# PIC32MK1024MCM064.net
KiCad netlist of a schematic drawn in Altium Designer
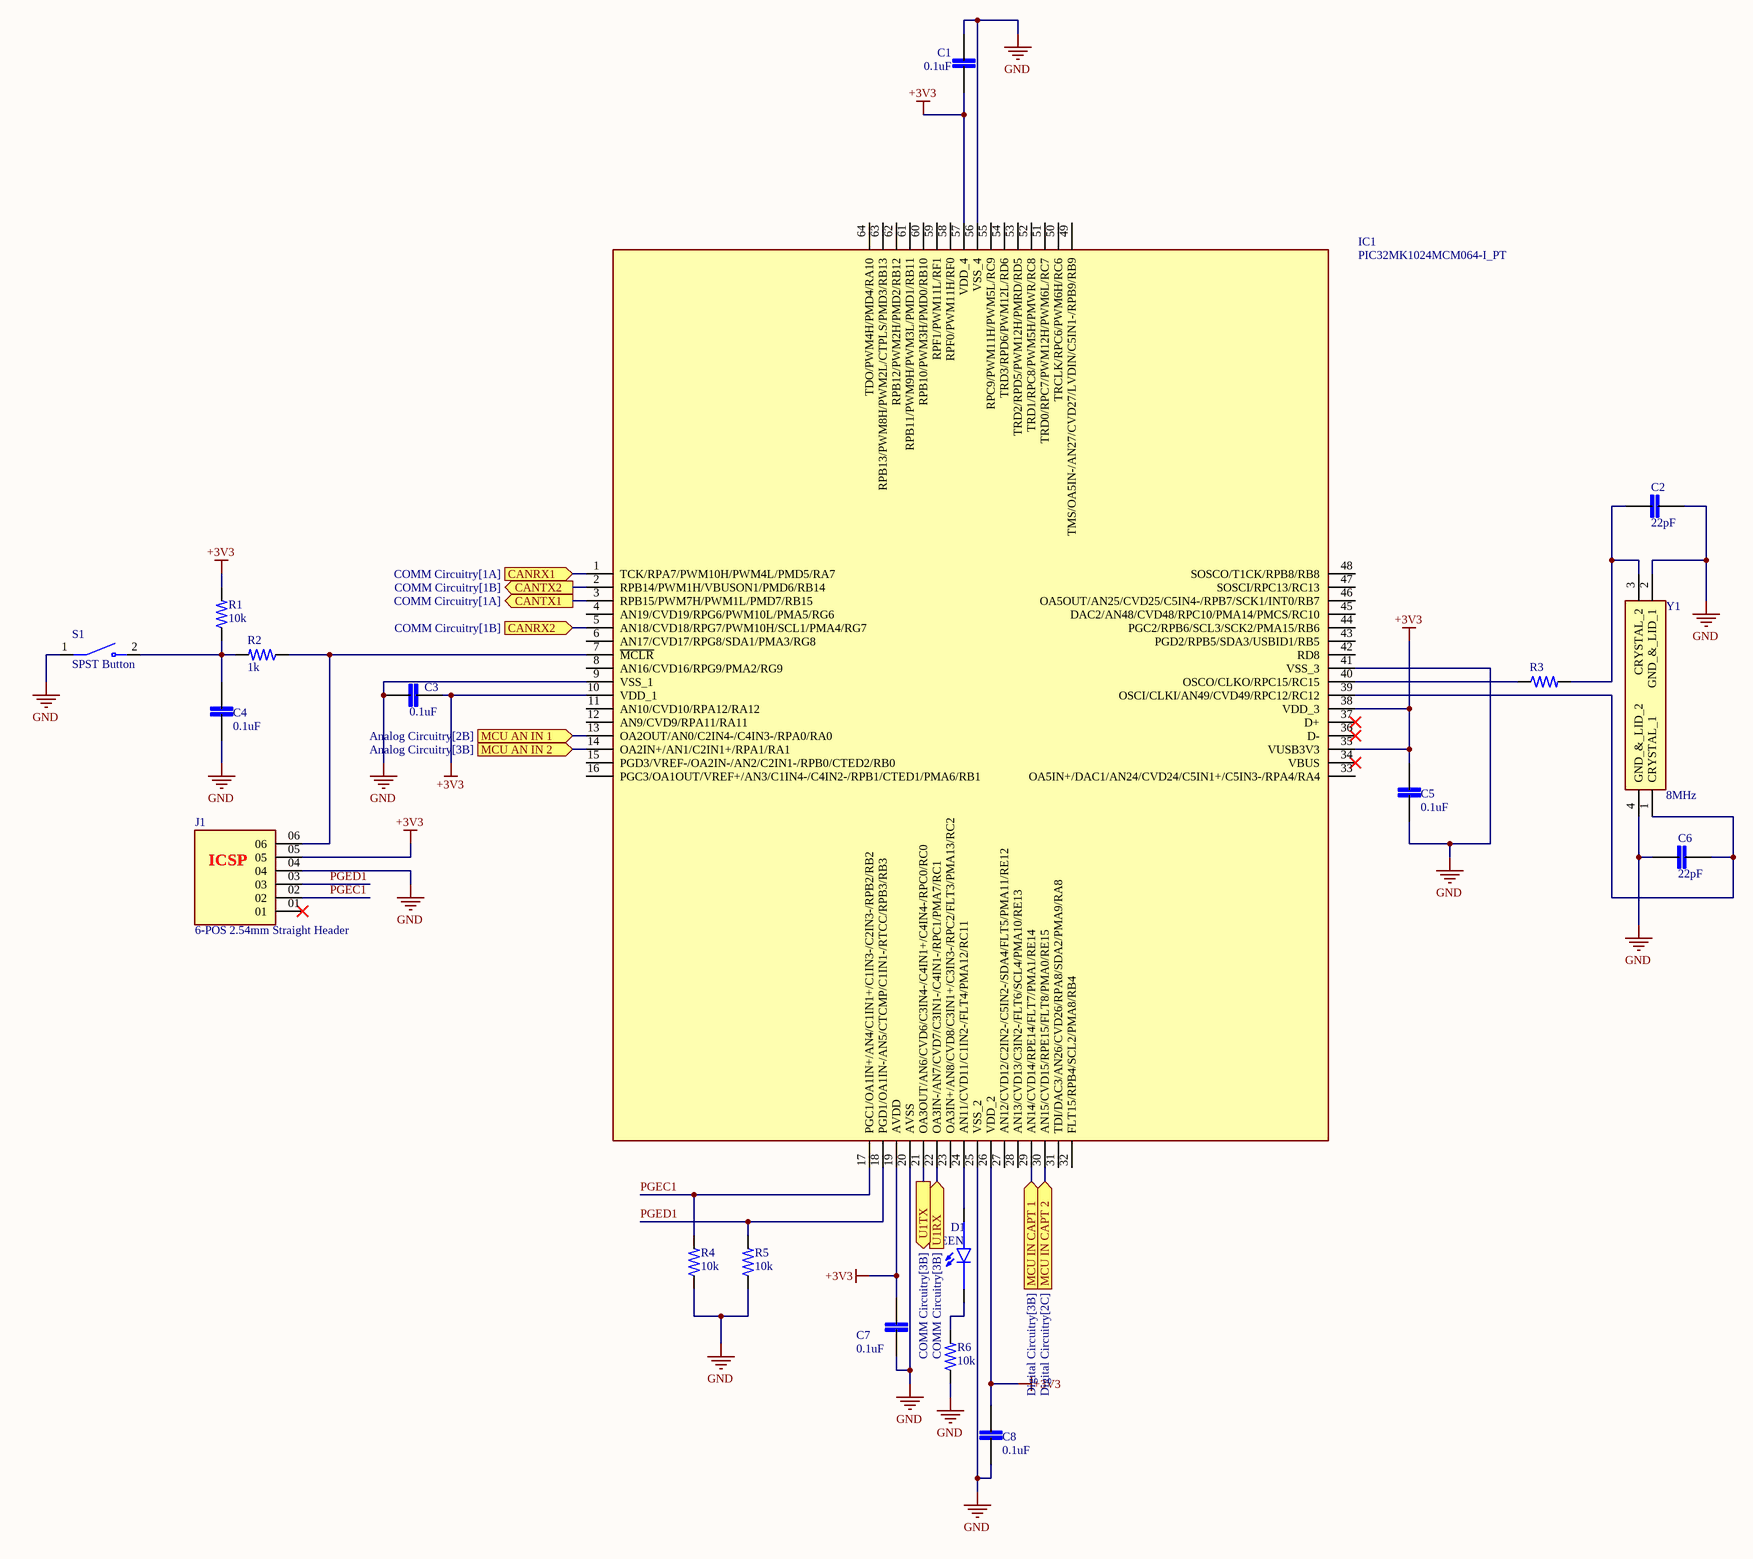
[diagram p0: PIC32MK1024MCM064.SchDoc]

(export (version "E")
  (design (tool "Eeschema 10.0.6"))
  (components
    (comp (ref "C1")
      (value "0.1uF")
      (footprint "0805")
      (fields (field (name "MP") "LD051A121KAB2A") (field (name "MF") "AVX"))
      (libsource (lib "") (part "0805_Capacitor_2"))
    )
    (comp (ref "C2")
      (value "22pF")
      (footprint "0805")
      (fields (field (name "MP") "LD051A121KAB2A") (field (name "MF") "AVX"))
      (libsource (lib "") (part "0805_Capacitor_1"))
    )
    (comp (ref "C3")
      (value "0.1uF")
      (footprint "0805")
      (fields (field (name "MP") "LD051A121KAB2A") (field (name "MF") "AVX"))
      (libsource (lib "") (part "0805_Capacitor_2"))
    )
    (comp (ref "C4")
      (value "0.1uF")
      (footprint "0805")
      (fields (field (name "MP") "LD051A121KAB2A") (field (name "MF") "AVX"))
      (libsource (lib "Capacitors SMD") (part "0805_Capacitor"))
    )
    (comp (ref "C5")
      (value "0.1uF")
      (footprint "0805")
      (fields (field (name "MP") "LD051A121KAB2A") (field (name "MF") "AVX"))
      (libsource (lib "Capacitors SMD") (part "0805_Capacitor"))
    )
    (comp (ref "C6")
      (value "22pF")
      (footprint "0805")
      (fields (field (name "MP") "LD051A121KAB2A") (field (name "MF") "AVX"))
      (libsource (lib "") (part "0805_Capacitor_1"))
    )
    (comp (ref "C7")
      (value "0.1uF")
      (footprint "0805")
      (fields (field (name "MP") "LD051A121KAB2A") (field (name "MF") "AVX"))
      (libsource (lib "Capacitors SMD") (part "0805_Capacitor"))
    )
    (comp (ref "C8")
      (value "0.1uF")
      (footprint "0805")
      (fields (field (name "MP") "LD051A121KAB2A") (field (name "MF") "AVX"))
      (libsource (lib "") (part "0805_Capacitor_1"))
    )
    (comp (ref "D1")
      (value "GREEN")
      (footprint "LED 0805")
      (description "LED Uni-Color Green 4-Pin Chip 0805 T/R")
      (fields (field (name "MP") "597-3305-607F"))
      (libsource (lib "LEDs SMD") (part "LED 0805"))
    )
    (comp (ref "IC1")
      (value "PIC32MK1024MCM064-I_PT")
      (footprint "Microcontrollers:PIC32MK1024MCM064-I_PT")
      (description "Integrated Circuit")
      (fields
        (field (name "MANUFACTURER_PART_NUMBER") "PIC32MK1024MCM064-I/PT")
        (field (name "MOUSER PART NUMBER") "579-2MK1024MCM064IPT")
      )
      (libsource (lib "Microcontrollers") (part "PIC32MK1024MCM064-I_PT"))
    )
    (comp (ref "J1")
      (value "6-POS 2.54mm Straight Header")
      (footprint "6-POS 2.54mm Header")
      (fields (field (name "MP") "HTSW10608SSLA") (field (name "MF") "Samtec"))
      (libsource (lib "Connectors Through Hole") (part "6-POS 2.54mm Straight Header"))
    )
    (comp (ref "R1")
      (value "10k")
      (footprint "0805")
      (fields
        (field (name "MP") "2-2176053-0")
        (field (name "TOLERANCE") "1%")
        (field (name "MF") "TE Connectivity")
      )
      (libsource (lib "Resistors SMD") (part "0805_Resistor"))
    )
    (comp (ref "R2")
      (value "1k")
      (footprint "0805")
      (fields
        (field (name "MP") "2-2176053-0")
        (field (name "TOLERANCE") "1%")
        (field (name "MF") "TE Connectivity")
      )
      (libsource (lib "Resistors SMD") (part "0805_Resistor"))
    )
    (comp (ref "R3")
      (value "0805_Resistor")
      (footprint "0805")
      (fields
        (field (name "MP") "2-2176053-0")
        (field (name "TOLERANCE") "1%")
        (field (name "MF") "TE Connectivity")
      )
      (libsource (lib "Resistors SMD") (part "0805_Resistor"))
    )
    (comp (ref "R4")
      (value "10k")
      (footprint "0805")
      (fields
        (field (name "MP") "2-2176053-0")
        (field (name "TOLERANCE") "1%")
        (field (name "MF") "TE Connectivity")
      )
      (libsource (lib "Resistors SMD") (part "0805_Resistor"))
    )
    (comp (ref "R5")
      (value "10k")
      (footprint "0805")
      (fields
        (field (name "MP") "2-2176053-0")
        (field (name "TOLERANCE") "1%")
        (field (name "MF") "TE Connectivity")
      )
      (libsource (lib "Resistors SMD") (part "0805_Resistor"))
    )
    (comp (ref "R6")
      (value "10k")
      (footprint "0805")
      (fields
        (field (name "MP") "2-2176053-0")
        (field (name "TOLERANCE") "1%")
        (field (name "MF") "TE Connectivity")
      )
      (libsource (lib "Resistors SMD") (part "0805_Resistor"))
    )
    (comp (ref "S1")
      (value "SPST Button")
      (footprint "Button SMD:SPST Button")
      (description "3mmX6mm")
      (fields (field (name "MP") "B3U-1000P"))
      (libsource (lib "Button SMD") (part "SPST Button"))
    )
    (comp (ref "Y1")
      (value "8MHz")
      (footprint "Crystals SMD:Crystal 5x3.2 - 4Pads")
      (description "Crystal or Oscillator")
      (fields
        (field (name "MANUFACTURER_PART_NUMBER") "830106162701")
        (field (name "MOUSER PART NUMBER") "710-830106162701")
      )
      (libsource (lib "Crystals SMD") (part "Crystal 5x3.2 - 4Pads"))
    )
  )
  (nets
    (net (code "1") (name "+3V3") (class "Default")
      (node (ref "C1") (pin "2") (pinfunction "2_2") (pintype "passive"))
      (node (ref "C3") (pin "1") (pinfunction "1_1") (pintype "passive"))
      (node (ref "C5") (pin "2") (pinfunction "2_2") (pintype "passive"))
      (node (ref "C7") (pin "2") (pinfunction "2_2") (pintype "passive"))
      (node (ref "C8") (pin "2") (pinfunction "2_2") (pintype "passive"))
      (node (ref "IC1") (pin "10") (pinfunction "VDD_1_10") (pintype "passive"))
      (node (ref "IC1") (pin "19") (pinfunction "AVDD_19") (pintype "passive"))
      (node (ref "IC1") (pin "26") (pinfunction "VDD_2_26") (pintype "passive"))
      (node (ref "IC1") (pin "35") (pinfunction "VUSB3V3_35") (pintype "passive"))
      (node (ref "IC1") (pin "38") (pinfunction "VDD_3_38") (pintype "passive"))
      (node (ref "IC1") (pin "57") (pinfunction "VDD_4_57") (pintype "passive"))
      (node (ref "J1") (pin "05") (pinfunction "05_05") (pintype "passive"))
      (node (ref "R1") (pin "2") (pinfunction "2_2") (pintype "passive"))
    )
    (net (code "2") (name "/CANRX1") (class "Default")
      (node (ref "IC1") (pin "1") (pinfunction "TCK/RPA7/PWM10H/PWM4L/PMD5/RA7_1") (pintype "passive"))
    )
    (net (code "3") (name "/CANRX2") (class "Default")
      (node (ref "IC1") (pin "5") (pinfunction "AN18/CVD18/RPG7/PWM10H/SCL1/PMA4/RG7_5") (pintype "passive"))
    )
    (net (code "4") (name "/CANTX1") (class "Default")
      (node (ref "IC1") (pin "3") (pinfunction "RPB15/PWM7H/PWM1L/PMD7/RB15_3") (pintype "passive"))
    )
    (net (code "5") (name "/CANTX2") (class "Default")
      (node (ref "IC1") (pin "2") (pinfunction "RPB14/PWM1H/VBUSON1/PMD6/RB14_2") (pintype "passive"))
    )
    (net (code "6") (name "/MCU AN IN 1") (class "Default")
      (node (ref "IC1") (pin "13") (pinfunction "OA2OUT/AN0/C2IN4-/C4IN3-/RPA0/RA0_13") (pintype "passive"))
    )
    (net (code "7") (name "/MCU AN IN 2") (class "Default")
      (node (ref "IC1") (pin "14") (pinfunction "OA2IN+/AN1/C2IN1+/RPA1/RA1_14") (pintype "passive"))
    )
    (net (code "8") (name "/MCU IN CAPT 1") (class "Default")
      (node (ref "IC1") (pin "29") (pinfunction "AN14/CVD14/RPE14/FLT7/PMA1/RE14_29") (pintype "passive"))
    )
    (net (code "9") (name "/MCU IN CAPT 2") (class "Default")
      (node (ref "IC1") (pin "30") (pinfunction "AN15/CVD15/RPE15/FLT8/PMA0/RE15_30") (pintype "passive"))
    )
    (net (code "10") (name "/PGEC1") (class "Default")
      (node (ref "IC1") (pin "17") (pinfunction "PGC1/OA1IN+/AN4/C1IN1+/C1IN3-/C2IN3-/RPB2/RB2_17") (pintype "passive"))
      (node (ref "J1") (pin "02") (pinfunction "02_02") (pintype "passive"))
      (node (ref "R4") (pin "2") (pinfunction "2_2") (pintype "passive"))
    )
    (net (code "11") (name "/PGED1") (class "Default")
      (node (ref "IC1") (pin "18") (pinfunction "PGD1/OA1IN-/AN5/CTCMP/C1IN1-/RTCC/RPB3/RB3_18") (pintype "passive"))
      (node (ref "J1") (pin "03") (pinfunction "03_03") (pintype "passive"))
      (node (ref "R5") (pin "2") (pinfunction "2_2") (pintype "passive"))
    )
    (net (code "12") (name "/U1RX") (class "Default")
      (node (ref "IC1") (pin "22") (pinfunction "OA3IN-/AN7/CVD7/C3IN1-/C4IN1-/RPC1/PMA7/RC1_22") (pintype "passive"))
    )
    (net (code "13") (name "/U1TX") (class "Default")
      (node (ref "IC1") (pin "21") (pinfunction "OA3OUT/AN6/CVD6/C3IN4-/C4IN1+/C4IN4-/RPC0/RC0_21") (pintype "passive"))
    )
    (net (code "14") (name "GND") (class "Default")
      (node (ref "C1") (pin "1") (pinfunction "1_1") (pintype "passive"))
      (node (ref "C2") (pin "2") (pinfunction "2_2") (pintype "passive"))
      (node (ref "C3") (pin "2") (pinfunction "2_2") (pintype "passive"))
      (node (ref "C4") (pin "1") (pinfunction "1_1") (pintype "passive"))
      (node (ref "C5") (pin "1") (pinfunction "1_1") (pintype "passive"))
      (node (ref "C6") (pin "1") (pinfunction "1_1") (pintype "passive"))
      (node (ref "C7") (pin "1") (pinfunction "1_1") (pintype "passive"))
      (node (ref "C8") (pin "1") (pinfunction "1_1") (pintype "passive"))
      (node (ref "IC1") (pin "20") (pinfunction "AVSS_20") (pintype "passive"))
      (node (ref "IC1") (pin "25") (pinfunction "VSS_2_25") (pintype "passive"))
      (node (ref "IC1") (pin "41") (pinfunction "VSS_3_41") (pintype "passive"))
      (node (ref "IC1") (pin "56") (pinfunction "VSS_4_56") (pintype "passive"))
      (node (ref "IC1") (pin "9") (pinfunction "VSS_1_9") (pintype "passive"))
      (node (ref "J1") (pin "04") (pinfunction "04_04") (pintype "passive"))
      (node (ref "R4") (pin "1") (pinfunction "1_1") (pintype "passive"))
      (node (ref "R5") (pin "1") (pinfunction "1_1") (pintype "passive"))
      (node (ref "R6") (pin "1") (pinfunction "1_1") (pintype "passive"))
      (node (ref "S1") (pin "1") (pinfunction "1_1") (pintype "passive"))
      (node (ref "Y1") (pin "2") (pinfunction "GND_&_LID_1_2") (pintype "passive"))
      (node (ref "Y1") (pin "4") (pinfunction "GND_&_LID_2_4") (pintype "passive"))
    )
    (net (code "15") (name "Net-(C4-Pad2)") (class "Default")
      (node (ref "C4") (pin "2") (pinfunction "2_2") (pintype "passive"))
      (node (ref "R1") (pin "1") (pinfunction "1_1") (pintype "passive"))
      (node (ref "R2") (pin "2") (pinfunction "2_2") (pintype "passive"))
      (node (ref "S1") (pin "2") (pinfunction "2_2") (pintype "passive"))
    )
    (net (code "16") (name "Net-(D1-PadC)") (class "Default")
      (node (ref "D1") (pin "C") (pinfunction "C_C") (pintype "passive"))
      (node (ref "R6") (pin "2") (pinfunction "2_2") (pintype "passive"))
    )
    (net (code "17") (name "Net-(IC1-AN11{slash}CVD11{slash}C1IN2-{slash}FLT4{slash}PMA12{slash}RC11)") (class "Default")
      (node (ref "D1") (pin "A") (pinfunction "A_A") (pintype "passive"))
      (node (ref "IC1") (pin "24") (pinfunction "AN11/CVD11/C1IN2-/FLT4/PMA12/RC11_24") (pintype "passive"))
    )
    (net (code "18") (name "Net-(IC1-OSCI{slash}CLKI{slash}AN49{slash}CVD49{slash}RPC12{slash}RC12)") (class "Default")
      (node (ref "C6") (pin "2") (pinfunction "2_2") (pintype "passive"))
      (node (ref "IC1") (pin "39") (pinfunction "OSCI/CLKI/AN49/CVD49/RPC12/RC12_39") (pintype "passive"))
      (node (ref "Y1") (pin "1") (pinfunction "CRYSTAL_1_1") (pintype "passive"))
    )
    (net (code "19") (name "Net-(IC1-OSCO{slash}CLKO{slash}RPC15{slash}RC15)") (class "Default")
      (node (ref "IC1") (pin "40") (pinfunction "OSCO/CLKO/RPC15/RC15_40") (pintype "passive"))
      (node (ref "R3") (pin "1") (pinfunction "1_1") (pintype "passive"))
    )
    (net (code "20") (name "Net-(IC1-~{MCLR})") (class "Default")
      (node (ref "IC1") (pin "7") (pinfunction "~{MCLR}_7") (pintype "passive"))
      (node (ref "J1") (pin "06") (pinfunction "06_06") (pintype "passive"))
      (node (ref "R2") (pin "1") (pinfunction "1_1") (pintype "passive"))
    )
    (net (code "21") (name "Net-(Y1-CRYSTAL_2)") (class "Default")
      (node (ref "C2") (pin "1") (pinfunction "1_1") (pintype "passive"))
      (node (ref "R3") (pin "2") (pinfunction "2_2") (pintype "passive"))
      (node (ref "Y1") (pin "3") (pinfunction "CRYSTAL_2_3") (pintype "passive"))
    )
    (net (code "22") (name "unconnected-(IC1-AN9{slash}CVD9{slash}RPA11{slash}RA11-Pad12)") (class "Default")
      (node (ref "IC1") (pin "12") (pinfunction "AN9/CVD9/RPA11/RA11_12") (pintype "passive"))
    )
    (net (code "23") (name "unconnected-(IC1-AN10{slash}CVD10{slash}RPA12{slash}RA12-Pad11)") (class "Default")
      (node (ref "IC1") (pin "11") (pinfunction "AN10/CVD10/RPA12/RA12_11") (pintype "passive"))
    )
    (net (code "24") (name "unconnected-(IC1-AN12{slash}CVD12{slash}C2IN2-{slash}C5IN2-{slash}SDA4{slash}FLT5{slash}PMA11{slash}RE12-Pad27)") (class "Default")
      (node (ref "IC1") (pin "27") (pinfunction "AN12/CVD12/C2IN2-/C5IN2-/SDA4/FLT5/PMA11/RE12_27") (pintype "passive"))
    )
    (net (code "25") (name "unconnected-(IC1-AN13{slash}CVD13{slash}C3IN2-{slash}FLT6{slash}SCL4{slash}PMA10{slash}RE13-Pad28)") (class "Default")
      (node (ref "IC1") (pin "28") (pinfunction "AN13/CVD13/C3IN2-/FLT6/SCL4/PMA10/RE13_28") (pintype "passive"))
    )
    (net (code "26") (name "unconnected-(IC1-AN16{slash}CVD16{slash}RPG9{slash}PMA2{slash}RG9-Pad8)") (class "Default")
      (node (ref "IC1") (pin "8") (pinfunction "AN16/CVD16/RPG9/PMA2/RG9_8") (pintype "passive"))
    )
    (net (code "27") (name "unconnected-(IC1-AN17{slash}CVD17{slash}RPG8{slash}SDA1{slash}PMA3{slash}RG8-Pad6)") (class "Default")
      (node (ref "IC1") (pin "6") (pinfunction "AN17/CVD17/RPG8/SDA1/PMA3/RG8_6") (pintype "passive"))
    )
    (net (code "28") (name "unconnected-(IC1-AN19{slash}CVD19{slash}RPG6{slash}PWM10L{slash}PMA5{slash}RG6-Pad4)") (class "Default")
      (node (ref "IC1") (pin "4") (pinfunction "AN19/CVD19/RPG6/PWM10L/PMA5/RG6_4") (pintype "passive"))
    )
    (net (code "29") (name "unconnected-(IC1-D+-Pad37)") (class "Default")
      (node (ref "IC1") (pin "37") (pinfunction "D+_37") (pintype "passive+no_connect"))
    )
    (net (code "30") (name "unconnected-(IC1-D--Pad36)") (class "Default")
      (node (ref "IC1") (pin "36") (pinfunction "D-_36") (pintype "passive+no_connect"))
    )
    (net (code "31") (name "unconnected-(IC1-DAC2{slash}AN48{slash}CVD48{slash}RPC10{slash}PMA14{slash}PMCS{slash}RC10-Pad45)") (class "Default")
      (node (ref "IC1") (pin "45") (pinfunction "DAC2/AN48/CVD48/RPC10/PMA14/PMCS/RC10_45") (pintype "passive"))
    )
    (net (code "32") (name "unconnected-(IC1-FLT15{slash}RPB4{slash}SCL2{slash}PMA8{slash}RB4-Pad32)") (class "Default")
      (node (ref "IC1") (pin "32") (pinfunction "FLT15/RPB4/SCL2/PMA8/RB4_32") (pintype "passive"))
    )
    (net (code "33") (name "unconnected-(IC1-OA3IN+{slash}AN8{slash}CVD8{slash}C3IN1+{slash}C3IN3-{slash}RPC2{slash}FLT3{slash}PMA13{slash}RC2-Pad23)") (class "Default")
      (node (ref "IC1") (pin "23") (pinfunction "OA3IN+/AN8/CVD8/C3IN1+/C3IN3-/RPC2/FLT3/PMA13/RC2_23") (pintype "passive"))
    )
    (net (code "34") (name "unconnected-(IC1-OA5IN+{slash}DAC1{slash}AN24{slash}CVD24{slash}C5IN1+{slash}C5IN3-{slash}RPA4{slash}RA4-Pad33)") (class "Default")
      (node (ref "IC1") (pin "33") (pinfunction "OA5IN+/DAC1/AN24/CVD24/C5IN1+/C5IN3-/RPA4/RA4_33") (pintype "passive"))
    )
    (net (code "35") (name "unconnected-(IC1-OA5OUT{slash}AN25{slash}CVD25{slash}C5IN4-{slash}RPB7{slash}SCK1{slash}INT0{slash}RB7-Pad46)") (class "Default")
      (node (ref "IC1") (pin "46") (pinfunction "OA5OUT/AN25/CVD25/C5IN4-/RPB7/SCK1/INT0/RB7_46") (pintype "passive"))
    )
    (net (code "36") (name "unconnected-(IC1-PGC2{slash}RPB6{slash}SCL3{slash}SCK2{slash}PMA15{slash}RB6-Pad44)") (class "Default")
      (node (ref "IC1") (pin "44") (pinfunction "PGC2/RPB6/SCL3/SCK2/PMA15/RB6_44") (pintype "passive"))
    )
    (net (code "37") (name "unconnected-(IC1-PGC3{slash}OA1OUT{slash}VREF+{slash}AN3{slash}C1IN4-{slash}C4IN2-{slash}RPB1{slash}CTED1{slash}PMA6{slash}RB1-Pad16)") (class "Default")
      (node (ref "IC1") (pin "16") (pinfunction "PGC3/OA1OUT/VREF+/AN3/C1IN4-/C4IN2-/RPB1/CTED1/PMA6/RB1_16") (pintype "passive"))
    )
    (net (code "38") (name "unconnected-(IC1-PGD2{slash}RPB5{slash}SDA3{slash}USBID1{slash}RB5-Pad43)") (class "Default")
      (node (ref "IC1") (pin "43") (pinfunction "PGD2/RPB5/SDA3/USBID1/RB5_43") (pintype "passive"))
    )
    (net (code "39") (name "unconnected-(IC1-PGD3{slash}VREF-{slash}OA2IN-{slash}AN2{slash}C2IN1-{slash}RPB0{slash}CTED2{slash}RB0-Pad15)") (class "Default")
      (node (ref "IC1") (pin "15") (pinfunction "PGD3/VREF-/OA2IN-/AN2/C2IN1-/RPB0/CTED2/RB0_15") (pintype "passive"))
    )
    (net (code "40") (name "unconnected-(IC1-RD8-Pad42)") (class "Default")
      (node (ref "IC1") (pin "42") (pinfunction "RD8_42") (pintype "passive"))
    )
    (net (code "41") (name "unconnected-(IC1-RPB10{slash}PWM3H{slash}PMD0{slash}RB10-Pad60)") (class "Default")
      (node (ref "IC1") (pin "60") (pinfunction "RPB10/PWM3H/PMD0/RB10_60") (pintype "passive"))
    )
    (net (code "42") (name "unconnected-(IC1-RPB11{slash}PWM9H{slash}PWM3L{slash}PMD1{slash}RB11-Pad61)") (class "Default")
      (node (ref "IC1") (pin "61") (pinfunction "RPB11/PWM9H/PWM3L/PMD1/RB11_61") (pintype "passive"))
    )
    (net (code "43") (name "unconnected-(IC1-RPB12{slash}PWM2H{slash}PMD2{slash}RB12-Pad62)") (class "Default")
      (node (ref "IC1") (pin "62") (pinfunction "RPB12/PWM2H/PMD2/RB12_62") (pintype "passive"))
    )
    (net (code "44") (name "unconnected-(IC1-RPB13{slash}PWM8H{slash}PWM2L{slash}CTPLS{slash}PMD3{slash}RB13-Pad63)") (class "Default")
      (node (ref "IC1") (pin "63") (pinfunction "RPB13/PWM8H/PWM2L/CTPLS/PMD3/RB13_63") (pintype "passive"))
    )
    (net (code "45") (name "unconnected-(IC1-RPC9{slash}PWM11H{slash}PWM5L{slash}RC9-Pad55)") (class "Default")
      (node (ref "IC1") (pin "55") (pinfunction "RPC9/PWM11H/PWM5L/RC9_55") (pintype "passive"))
    )
    (net (code "46") (name "unconnected-(IC1-RPF0{slash}PWM11H{slash}RF0-Pad58)") (class "Default")
      (node (ref "IC1") (pin "58") (pinfunction "RPF0/PWM11H/RF0_58") (pintype "passive"))
    )
    (net (code "47") (name "unconnected-(IC1-RPF1{slash}PWM11L{slash}RF1-Pad59)") (class "Default")
      (node (ref "IC1") (pin "59") (pinfunction "RPF1/PWM11L/RF1_59") (pintype "passive"))
    )
    (net (code "48") (name "unconnected-(IC1-SOSCI{slash}RPC13{slash}RC13-Pad47)") (class "Default")
      (node (ref "IC1") (pin "47") (pinfunction "SOSCI/RPC13/RC13_47") (pintype "passive"))
    )
    (net (code "49") (name "unconnected-(IC1-SOSCO{slash}T1CK{slash}RPB8{slash}RB8-Pad48)") (class "Default")
      (node (ref "IC1") (pin "48") (pinfunction "SOSCO/T1CK/RPB8/RB8_48") (pintype "passive"))
    )
    (net (code "50") (name "unconnected-(IC1-TDI{slash}DAC3{slash}AN26{slash}CVD26{slash}RPA8{slash}SDA2{slash}PMA9{slash}RA8-Pad31)") (class "Default")
      (node (ref "IC1") (pin "31") (pinfunction "TDI/DAC3/AN26/CVD26/RPA8/SDA2/PMA9/RA8_31") (pintype "passive"))
    )
    (net (code "51") (name "unconnected-(IC1-TDO{slash}PWM4H{slash}PMD4{slash}RA10-Pad64)") (class "Default")
      (node (ref "IC1") (pin "64") (pinfunction "TDO/PWM4H/PMD4/RA10_64") (pintype "passive"))
    )
    (net (code "52") (name "unconnected-(IC1-TMS{slash}OA5IN-{slash}AN27{slash}CVD27{slash}LVDIN{slash}C5IN1-{slash}RPB9{slash}RB9-Pad49)") (class "Default")
      (node (ref "IC1") (pin "49") (pinfunction "TMS/OA5IN-/AN27/CVD27/LVDIN/C5IN1-/RPB9/RB9_49") (pintype "passive"))
    )
    (net (code "53") (name "unconnected-(IC1-TRCLK{slash}RPC6{slash}PWM6H{slash}RC6-Pad50)") (class "Default")
      (node (ref "IC1") (pin "50") (pinfunction "TRCLK/RPC6/PWM6H/RC6_50") (pintype "passive"))
    )
    (net (code "54") (name "unconnected-(IC1-TRD0{slash}RPC7{slash}PWM12H{slash}PWM6L{slash}RC7-Pad51)") (class "Default")
      (node (ref "IC1") (pin "51") (pinfunction "TRD0/RPC7/PWM12H/PWM6L/RC7_51") (pintype "passive"))
    )
    (net (code "55") (name "unconnected-(IC1-TRD1{slash}RPC8{slash}PWM5H{slash}PMWR{slash}RC8-Pad52)") (class "Default")
      (node (ref "IC1") (pin "52") (pinfunction "TRD1/RPC8/PWM5H/PMWR/RC8_52") (pintype "passive"))
    )
    (net (code "56") (name "unconnected-(IC1-TRD2{slash}RPD5{slash}PWM12H{slash}PMRD{slash}RD5-Pad53)") (class "Default")
      (node (ref "IC1") (pin "53") (pinfunction "TRD2/RPD5/PWM12H/PMRD/RD5_53") (pintype "passive"))
    )
    (net (code "57") (name "unconnected-(IC1-TRD3{slash}RPD6{slash}PWM12L{slash}RD6-Pad54)") (class "Default")
      (node (ref "IC1") (pin "54") (pinfunction "TRD3/RPD6/PWM12L/RD6_54") (pintype "passive"))
    )
    (net (code "58") (name "unconnected-(IC1-VBUS-Pad34)") (class "Default")
      (node (ref "IC1") (pin "34") (pinfunction "VBUS_34") (pintype "passive+no_connect"))
    )
    (net (code "59") (name "unconnected-(J1-Pad01)") (class "Default")
      (node (ref "J1") (pin "01") (pinfunction "01_01") (pintype "passive+no_connect"))
    )
  )
)
